# DSP_GPIO_Part1.net
KiCad netlist of a schematic drawn in Altium Designer
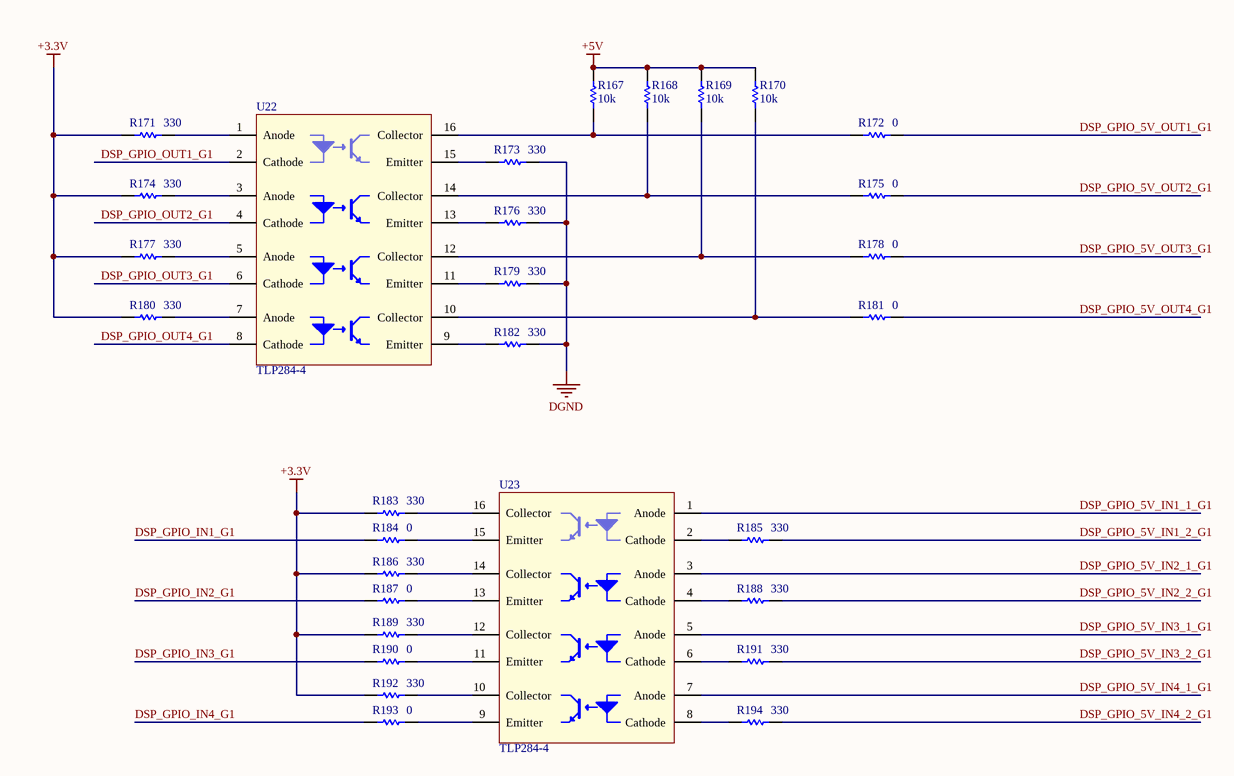
[diagram p0: DSP_GPIO_Part1.SchDoc]

(export (version "E")
  (design (tool "Eeschema 10.0.6"))
  (components
    (comp (ref "R167")
      (value "10k")
      (footprint "1608[0603]")
      (description "Resistor")
      (fields (field (name "Comment") "Res1") (field (name "PUBLISHER") "Altium Limited"))
      (libsource (lib "Miscellaneous Devices") (part "Res1"))
    )
    (comp (ref "R168")
      (value "10k")
      (footprint "1608[0603]")
      (description "Resistor")
      (fields (field (name "Comment") "Res1") (field (name "PUBLISHER") "Altium Limited"))
      (libsource (lib "Miscellaneous Devices") (part "Res1"))
    )
    (comp (ref "R169")
      (value "10k")
      (footprint "1608[0603]")
      (description "Resistor")
      (fields (field (name "Comment") "Res1") (field (name "PUBLISHER") "Altium Limited"))
      (libsource (lib "Miscellaneous Devices") (part "Res1"))
    )
    (comp (ref "R170")
      (value "10k")
      (footprint "1608[0603]")
      (description "Resistor")
      (fields (field (name "Comment") "Res1") (field (name "PUBLISHER") "Altium Limited"))
      (libsource (lib "Miscellaneous Devices") (part "Res1"))
    )
    (comp (ref "R171")
      (value "330")
      (footprint "1608[0603]")
      (description "Resistor")
      (fields (field (name "Comment") "Res1") (field (name "PUBLISHER") "Altium Limited"))
      (libsource (lib "Miscellaneous Devices") (part "Res1"))
    )
    (comp (ref "R172")
      (value "0")
      (footprint "1608[0603]")
      (description "Resistor")
      (fields (field (name "Comment") "Res1") (field (name "PUBLISHER") "Altium Limited"))
      (libsource (lib "Miscellaneous Devices") (part "Res1"))
    )
    (comp (ref "R173")
      (value "330")
      (footprint "1608[0603]")
      (description "Resistor")
      (fields (field (name "Comment") "Res1") (field (name "PUBLISHER") "Altium Limited"))
      (libsource (lib "Miscellaneous Devices") (part "Res1"))
    )
    (comp (ref "R174")
      (value "330")
      (footprint "1608[0603]")
      (description "Resistor")
      (fields (field (name "Comment") "Res1") (field (name "PUBLISHER") "Altium Limited"))
      (libsource (lib "Miscellaneous Devices") (part "Res1"))
    )
    (comp (ref "R175")
      (value "0")
      (footprint "1608[0603]")
      (description "Resistor")
      (fields (field (name "Comment") "Res1") (field (name "PUBLISHER") "Altium Limited"))
      (libsource (lib "Miscellaneous Devices") (part "Res1"))
    )
    (comp (ref "R176")
      (value "330")
      (footprint "1608[0603]")
      (description "Resistor")
      (fields (field (name "Comment") "Res1") (field (name "PUBLISHER") "Altium Limited"))
      (libsource (lib "Miscellaneous Devices") (part "Res1"))
    )
    (comp (ref "R177")
      (value "330")
      (footprint "1608[0603]")
      (description "Resistor")
      (fields (field (name "Comment") "Res1") (field (name "PUBLISHER") "Altium Limited"))
      (libsource (lib "Miscellaneous Devices") (part "Res1"))
    )
    (comp (ref "R178")
      (value "0")
      (footprint "1608[0603]")
      (description "Resistor")
      (fields (field (name "Comment") "Res1") (field (name "PUBLISHER") "Altium Limited"))
      (libsource (lib "Miscellaneous Devices") (part "Res1"))
    )
    (comp (ref "R179")
      (value "330")
      (footprint "1608[0603]")
      (description "Resistor")
      (fields (field (name "Comment") "Res1") (field (name "PUBLISHER") "Altium Limited"))
      (libsource (lib "Miscellaneous Devices") (part "Res1"))
    )
    (comp (ref "R180")
      (value "330")
      (footprint "1608[0603]")
      (description "Resistor")
      (fields (field (name "Comment") "Res1") (field (name "PUBLISHER") "Altium Limited"))
      (libsource (lib "Miscellaneous Devices") (part "Res1"))
    )
    (comp (ref "R181")
      (value "0")
      (footprint "1608[0603]")
      (description "Resistor")
      (fields (field (name "Comment") "Res1") (field (name "PUBLISHER") "Altium Limited"))
      (libsource (lib "Miscellaneous Devices") (part "Res1"))
    )
    (comp (ref "R182")
      (value "330")
      (footprint "1608[0603]")
      (description "Resistor")
      (fields (field (name "Comment") "Res1") (field (name "PUBLISHER") "Altium Limited"))
      (libsource (lib "Miscellaneous Devices") (part "Res1"))
    )
    (comp (ref "R183")
      (value "330")
      (footprint "1608[0603]")
      (description "Resistor")
      (fields (field (name "Comment") "Res1") (field (name "PUBLISHER") "Altium Limited"))
      (libsource (lib "Miscellaneous Devices") (part "Res1"))
    )
    (comp (ref "R184")
      (value "0")
      (footprint "1608[0603]")
      (description "Resistor")
      (fields (field (name "Comment") "Res1") (field (name "PUBLISHER") "Altium Limited"))
      (libsource (lib "Miscellaneous Devices") (part "Res1"))
    )
    (comp (ref "R185")
      (value "330")
      (footprint "1608[0603]")
      (description "Resistor")
      (fields (field (name "Comment") "Res1") (field (name "PUBLISHER") "Altium Limited"))
      (libsource (lib "Miscellaneous Devices") (part "Res1"))
    )
    (comp (ref "R186")
      (value "330")
      (footprint "1608[0603]")
      (description "Resistor")
      (fields (field (name "Comment") "Res1") (field (name "PUBLISHER") "Altium Limited"))
      (libsource (lib "Miscellaneous Devices") (part "Res1"))
    )
    (comp (ref "R187")
      (value "0")
      (footprint "1608[0603]")
      (description "Resistor")
      (fields (field (name "Comment") "Res1") (field (name "PUBLISHER") "Altium Limited"))
      (libsource (lib "Miscellaneous Devices") (part "Res1"))
    )
    (comp (ref "R188")
      (value "330")
      (footprint "1608[0603]")
      (description "Resistor")
      (fields (field (name "Comment") "Res1") (field (name "PUBLISHER") "Altium Limited"))
      (libsource (lib "Miscellaneous Devices") (part "Res1"))
    )
    (comp (ref "R189")
      (value "330")
      (footprint "1608[0603]")
      (description "Resistor")
      (fields (field (name "Comment") "Res1") (field (name "PUBLISHER") "Altium Limited"))
      (libsource (lib "Miscellaneous Devices") (part "Res1"))
    )
    (comp (ref "R190")
      (value "0")
      (footprint "1608[0603]")
      (description "Resistor")
      (fields (field (name "Comment") "Res1") (field (name "PUBLISHER") "Altium Limited"))
      (libsource (lib "Miscellaneous Devices") (part "Res1"))
    )
    (comp (ref "R191")
      (value "330")
      (footprint "1608[0603]")
      (description "Resistor")
      (fields (field (name "Comment") "Res1") (field (name "PUBLISHER") "Altium Limited"))
      (libsource (lib "Miscellaneous Devices") (part "Res1"))
    )
    (comp (ref "R192")
      (value "330")
      (footprint "1608[0603]")
      (description "Resistor")
      (fields (field (name "Comment") "Res1") (field (name "PUBLISHER") "Altium Limited"))
      (libsource (lib "Miscellaneous Devices") (part "Res1"))
    )
    (comp (ref "R193")
      (value "0")
      (footprint "1608[0603]")
      (description "Resistor")
      (fields (field (name "Comment") "Res1") (field (name "PUBLISHER") "Altium Limited"))
      (libsource (lib "Miscellaneous Devices") (part "Res1"))
    )
    (comp (ref "R194")
      (value "330")
      (footprint "1608[0603]")
      (description "Resistor")
      (fields (field (name "Comment") "Res1") (field (name "PUBLISHER") "Altium Limited"))
      (libsource (lib "Miscellaneous Devices") (part "Res1"))
    )
    (comp (ref "U22")
      (value "TLP284-4")
      (footprint "TLP284-4")
      (libsource (lib "DSP_FPGA_Lib") (part "TLP284-4"))
    )
    (comp (ref "U23")
      (value "TLP284-4")
      (footprint "TLP284-4")
      (libsource (lib "DSP_FPGA_Lib") (part "TLP284-4"))
    )
  )
  (nets
    (net (code "1") (name "+3.3V") (class "Default")
      (node (ref "R171") (pin "1") (pinfunction "1_1") (pintype "passive"))
      (node (ref "R174") (pin "1") (pinfunction "1_1") (pintype "passive"))
      (node (ref "R177") (pin "1") (pinfunction "1_1") (pintype "passive"))
      (node (ref "R180") (pin "1") (pinfunction "1_1") (pintype "passive"))
      (node (ref "R183") (pin "1") (pinfunction "1_1") (pintype "passive"))
      (node (ref "R186") (pin "1") (pinfunction "1_1") (pintype "passive"))
      (node (ref "R189") (pin "1") (pinfunction "1_1") (pintype "passive"))
      (node (ref "R192") (pin "1") (pinfunction "1_1") (pintype "passive"))
    )
    (net (code "2") (name "+5V") (class "Default")
      (node (ref "R167") (pin "2") (pinfunction "2_2") (pintype "passive"))
      (node (ref "R168") (pin "2") (pinfunction "2_2") (pintype "passive"))
      (node (ref "R169") (pin "2") (pinfunction "2_2") (pintype "passive"))
      (node (ref "R170") (pin "2") (pinfunction "2_2") (pintype "passive"))
    )
    (net (code "3") (name "/DSP_GPIO_5V_IN1_1_G1") (class "Default")
      (node (ref "U23") (pin "1") (pinfunction "Anode_1") (pintype "passive"))
    )
    (net (code "4") (name "/DSP_GPIO_5V_IN1_2_G1") (class "Default")
      (node (ref "R185") (pin "2") (pinfunction "2_2") (pintype "passive"))
    )
    (net (code "5") (name "/DSP_GPIO_5V_IN2_1_G1") (class "Default")
      (node (ref "U23") (pin "3") (pinfunction "Anode_3") (pintype "passive"))
    )
    (net (code "6") (name "/DSP_GPIO_5V_IN2_2_G1") (class "Default")
      (node (ref "R188") (pin "2") (pinfunction "2_2") (pintype "passive"))
    )
    (net (code "7") (name "/DSP_GPIO_5V_IN3_1_G1") (class "Default")
      (node (ref "U23") (pin "5") (pinfunction "Anode_5") (pintype "passive"))
    )
    (net (code "8") (name "/DSP_GPIO_5V_IN3_2_G1") (class "Default")
      (node (ref "R191") (pin "2") (pinfunction "2_2") (pintype "passive"))
    )
    (net (code "9") (name "/DSP_GPIO_5V_IN4_1_G1") (class "Default")
      (node (ref "U23") (pin "7") (pinfunction "Anode_7") (pintype "passive"))
    )
    (net (code "10") (name "/DSP_GPIO_5V_IN4_2_G1") (class "Default")
      (node (ref "R194") (pin "2") (pinfunction "2_2") (pintype "passive"))
    )
    (net (code "11") (name "/DSP_GPIO_5V_OUT1_G1") (class "Default")
      (node (ref "R172") (pin "2") (pinfunction "2_2") (pintype "passive"))
    )
    (net (code "12") (name "/DSP_GPIO_5V_OUT2_G1") (class "Default")
      (node (ref "R175") (pin "2") (pinfunction "2_2") (pintype "passive"))
    )
    (net (code "13") (name "/DSP_GPIO_5V_OUT3_G1") (class "Default")
      (node (ref "R178") (pin "2") (pinfunction "2_2") (pintype "passive"))
    )
    (net (code "14") (name "/DSP_GPIO_5V_OUT4_G1") (class "Default")
      (node (ref "R181") (pin "2") (pinfunction "2_2") (pintype "passive"))
    )
    (net (code "15") (name "/DSP_GPIO_IN1_G1") (class "Default")
      (node (ref "R184") (pin "1") (pinfunction "1_1") (pintype "passive"))
    )
    (net (code "16") (name "/DSP_GPIO_IN2_G1") (class "Default")
      (node (ref "R187") (pin "1") (pinfunction "1_1") (pintype "passive"))
    )
    (net (code "17") (name "/DSP_GPIO_IN3_G1") (class "Default")
      (node (ref "R190") (pin "1") (pinfunction "1_1") (pintype "passive"))
    )
    (net (code "18") (name "/DSP_GPIO_IN4_G1") (class "Default")
      (node (ref "R193") (pin "1") (pinfunction "1_1") (pintype "passive"))
    )
    (net (code "19") (name "/DSP_GPIO_OUT1_G1") (class "Default")
      (node (ref "U22") (pin "2") (pinfunction "Cathode_2") (pintype "passive"))
    )
    (net (code "20") (name "/DSP_GPIO_OUT2_G1") (class "Default")
      (node (ref "U22") (pin "4") (pinfunction "Cathode_4") (pintype "passive"))
    )
    (net (code "21") (name "/DSP_GPIO_OUT3_G1") (class "Default")
      (node (ref "U22") (pin "6") (pinfunction "Cathode_6") (pintype "passive"))
    )
    (net (code "22") (name "/DSP_GPIO_OUT4_G1") (class "Default")
      (node (ref "U22") (pin "8") (pinfunction "Cathode_8") (pintype "passive"))
    )
    (net (code "23") (name "DGND") (class "Default")
      (node (ref "R173") (pin "2") (pinfunction "2_2") (pintype "passive"))
      (node (ref "R176") (pin "2") (pinfunction "2_2") (pintype "passive"))
      (node (ref "R179") (pin "2") (pinfunction "2_2") (pintype "passive"))
      (node (ref "R182") (pin "2") (pinfunction "2_2") (pintype "passive"))
    )
    (net (code "24") (name "Net-(R167-Pad1)") (class "Default")
      (node (ref "R167") (pin "1") (pinfunction "1_1") (pintype "passive"))
      (node (ref "R172") (pin "1") (pinfunction "1_1") (pintype "passive"))
      (node (ref "U22") (pin "16") (pinfunction "Collector_16") (pintype "passive"))
    )
    (net (code "25") (name "Net-(R168-Pad1)") (class "Default")
      (node (ref "R168") (pin "1") (pinfunction "1_1") (pintype "passive"))
      (node (ref "R175") (pin "1") (pinfunction "1_1") (pintype "passive"))
      (node (ref "U22") (pin "14") (pinfunction "Collector_14") (pintype "passive"))
    )
    (net (code "26") (name "Net-(R169-Pad1)") (class "Default")
      (node (ref "R169") (pin "1") (pinfunction "1_1") (pintype "passive"))
      (node (ref "R178") (pin "1") (pinfunction "1_1") (pintype "passive"))
      (node (ref "U22") (pin "12") (pinfunction "Collector_12") (pintype "passive"))
    )
    (net (code "27") (name "Net-(R170-Pad1)") (class "Default")
      (node (ref "R170") (pin "1") (pinfunction "1_1") (pintype "passive"))
      (node (ref "R181") (pin "1") (pinfunction "1_1") (pintype "passive"))
      (node (ref "U22") (pin "10") (pinfunction "Collector_10") (pintype "passive"))
    )
    (net (code "28") (name "Net-(R171-Pad2)") (class "Default")
      (node (ref "R171") (pin "2") (pinfunction "2_2") (pintype "passive"))
      (node (ref "U22") (pin "1") (pinfunction "Anode_1") (pintype "passive"))
    )
    (net (code "29") (name "Net-(R173-Pad1)") (class "Default")
      (node (ref "R173") (pin "1") (pinfunction "1_1") (pintype "passive"))
      (node (ref "U22") (pin "15") (pinfunction "Emitter_15") (pintype "passive"))
    )
    (net (code "30") (name "Net-(R174-Pad2)") (class "Default")
      (node (ref "R174") (pin "2") (pinfunction "2_2") (pintype "passive"))
      (node (ref "U22") (pin "3") (pinfunction "Anode_3") (pintype "passive"))
    )
    (net (code "31") (name "Net-(R176-Pad1)") (class "Default")
      (node (ref "R176") (pin "1") (pinfunction "1_1") (pintype "passive"))
      (node (ref "U22") (pin "13") (pinfunction "Emitter_13") (pintype "passive"))
    )
    (net (code "32") (name "Net-(R177-Pad2)") (class "Default")
      (node (ref "R177") (pin "2") (pinfunction "2_2") (pintype "passive"))
      (node (ref "U22") (pin "5") (pinfunction "Anode_5") (pintype "passive"))
    )
    (net (code "33") (name "Net-(R179-Pad1)") (class "Default")
      (node (ref "R179") (pin "1") (pinfunction "1_1") (pintype "passive"))
      (node (ref "U22") (pin "11") (pinfunction "Emitter_11") (pintype "passive"))
    )
    (net (code "34") (name "Net-(R180-Pad2)") (class "Default")
      (node (ref "R180") (pin "2") (pinfunction "2_2") (pintype "passive"))
      (node (ref "U22") (pin "7") (pinfunction "Anode_7") (pintype "passive"))
    )
    (net (code "35") (name "Net-(R182-Pad1)") (class "Default")
      (node (ref "R182") (pin "1") (pinfunction "1_1") (pintype "passive"))
      (node (ref "U22") (pin "9") (pinfunction "Emitter_9") (pintype "passive"))
    )
    (net (code "36") (name "Net-(R183-Pad2)") (class "Default")
      (node (ref "R183") (pin "2") (pinfunction "2_2") (pintype "passive"))
      (node (ref "U23") (pin "16") (pinfunction "Collector_16") (pintype "passive"))
    )
    (net (code "37") (name "Net-(R184-Pad2)") (class "Default")
      (node (ref "R184") (pin "2") (pinfunction "2_2") (pintype "passive"))
      (node (ref "U23") (pin "15") (pinfunction "Emitter_15") (pintype "passive"))
    )
    (net (code "38") (name "Net-(R185-Pad1)") (class "Default")
      (node (ref "R185") (pin "1") (pinfunction "1_1") (pintype "passive"))
      (node (ref "U23") (pin "2") (pinfunction "Cathode_2") (pintype "passive"))
    )
    (net (code "39") (name "Net-(R186-Pad2)") (class "Default")
      (node (ref "R186") (pin "2") (pinfunction "2_2") (pintype "passive"))
      (node (ref "U23") (pin "14") (pinfunction "Collector_14") (pintype "passive"))
    )
    (net (code "40") (name "Net-(R187-Pad2)") (class "Default")
      (node (ref "R187") (pin "2") (pinfunction "2_2") (pintype "passive"))
      (node (ref "U23") (pin "13") (pinfunction "Emitter_13") (pintype "passive"))
    )
    (net (code "41") (name "Net-(R188-Pad1)") (class "Default")
      (node (ref "R188") (pin "1") (pinfunction "1_1") (pintype "passive"))
      (node (ref "U23") (pin "4") (pinfunction "Cathode_4") (pintype "passive"))
    )
    (net (code "42") (name "Net-(R189-Pad2)") (class "Default")
      (node (ref "R189") (pin "2") (pinfunction "2_2") (pintype "passive"))
      (node (ref "U23") (pin "12") (pinfunction "Collector_12") (pintype "passive"))
    )
    (net (code "43") (name "Net-(R190-Pad2)") (class "Default")
      (node (ref "R190") (pin "2") (pinfunction "2_2") (pintype "passive"))
      (node (ref "U23") (pin "11") (pinfunction "Emitter_11") (pintype "passive"))
    )
    (net (code "44") (name "Net-(R191-Pad1)") (class "Default")
      (node (ref "R191") (pin "1") (pinfunction "1_1") (pintype "passive"))
      (node (ref "U23") (pin "6") (pinfunction "Cathode_6") (pintype "passive"))
    )
    (net (code "45") (name "Net-(R192-Pad2)") (class "Default")
      (node (ref "R192") (pin "2") (pinfunction "2_2") (pintype "passive"))
      (node (ref "U23") (pin "10") (pinfunction "Collector_10") (pintype "passive"))
    )
    (net (code "46") (name "Net-(R193-Pad2)") (class "Default")
      (node (ref "R193") (pin "2") (pinfunction "2_2") (pintype "passive"))
      (node (ref "U23") (pin "9") (pinfunction "Emitter_9") (pintype "passive"))
    )
    (net (code "47") (name "Net-(R194-Pad1)") (class "Default")
      (node (ref "R194") (pin "1") (pinfunction "1_1") (pintype "passive"))
      (node (ref "U23") (pin "8") (pinfunction "Cathode_8") (pintype "passive"))
    )
  )
)
